# SCH_glacierone_2023-07-03.net
KiCad netlist of a schematic drawn in EasyEDA
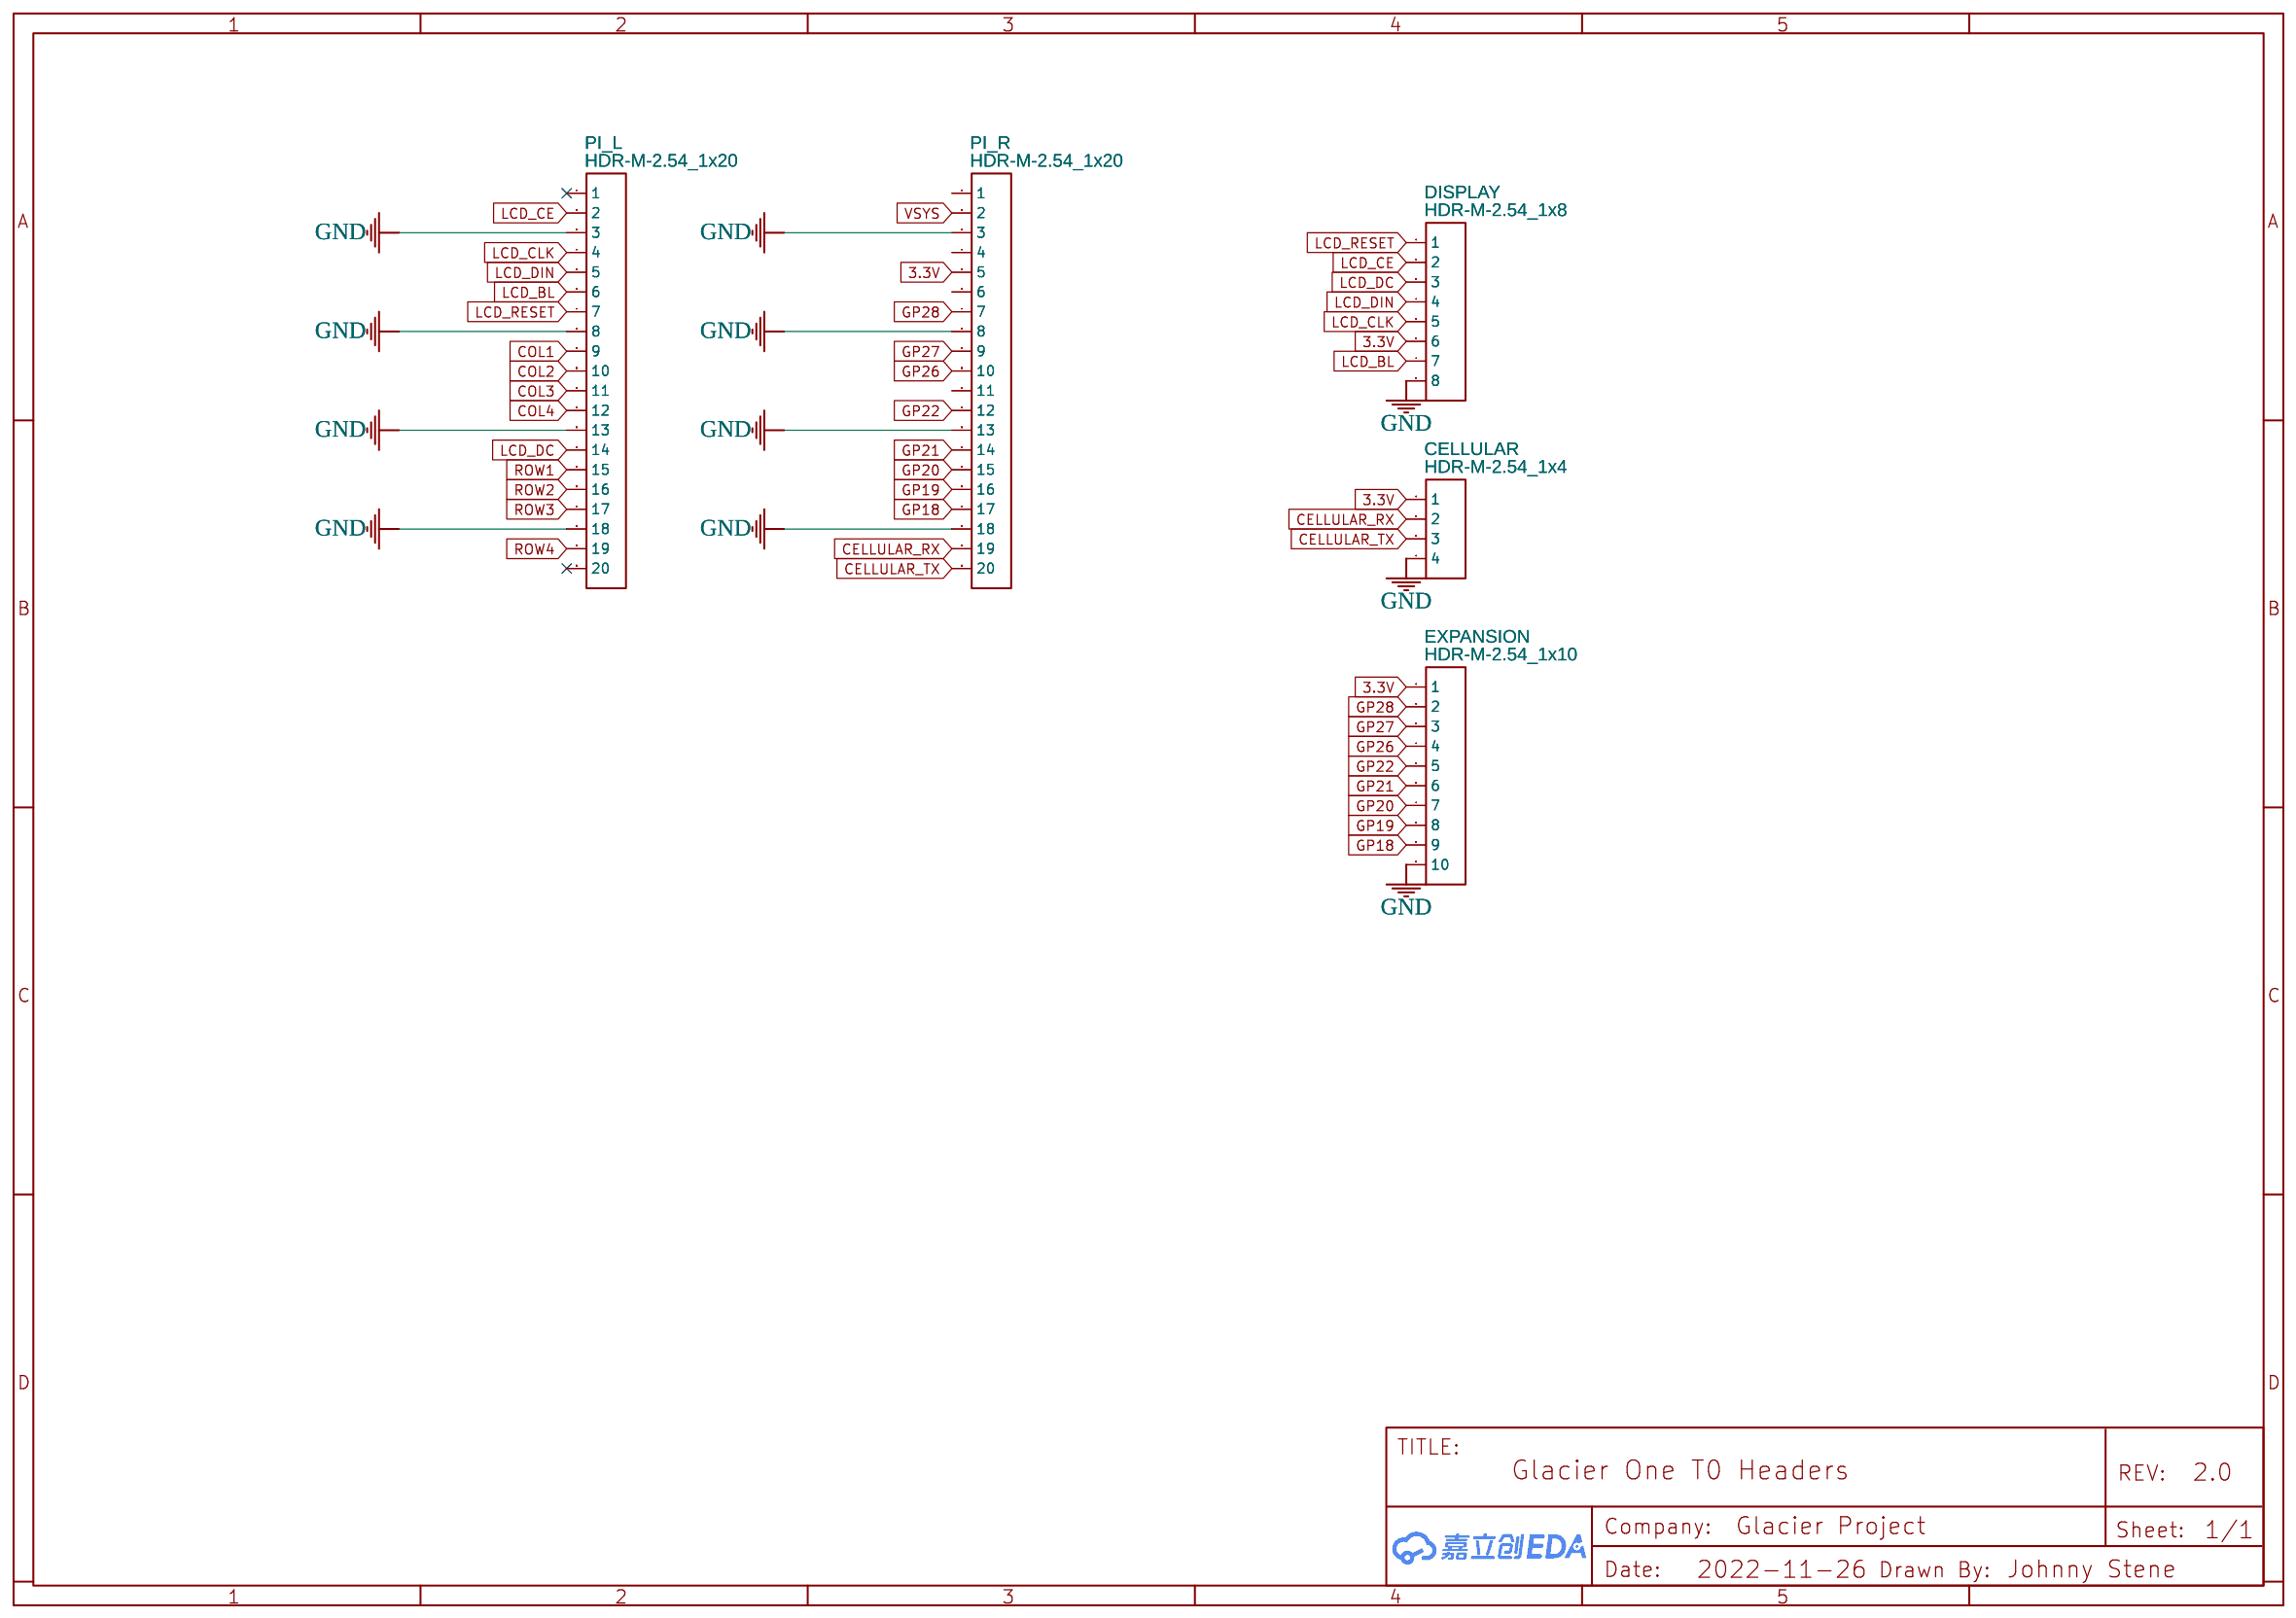
[diagram p0: Headers]
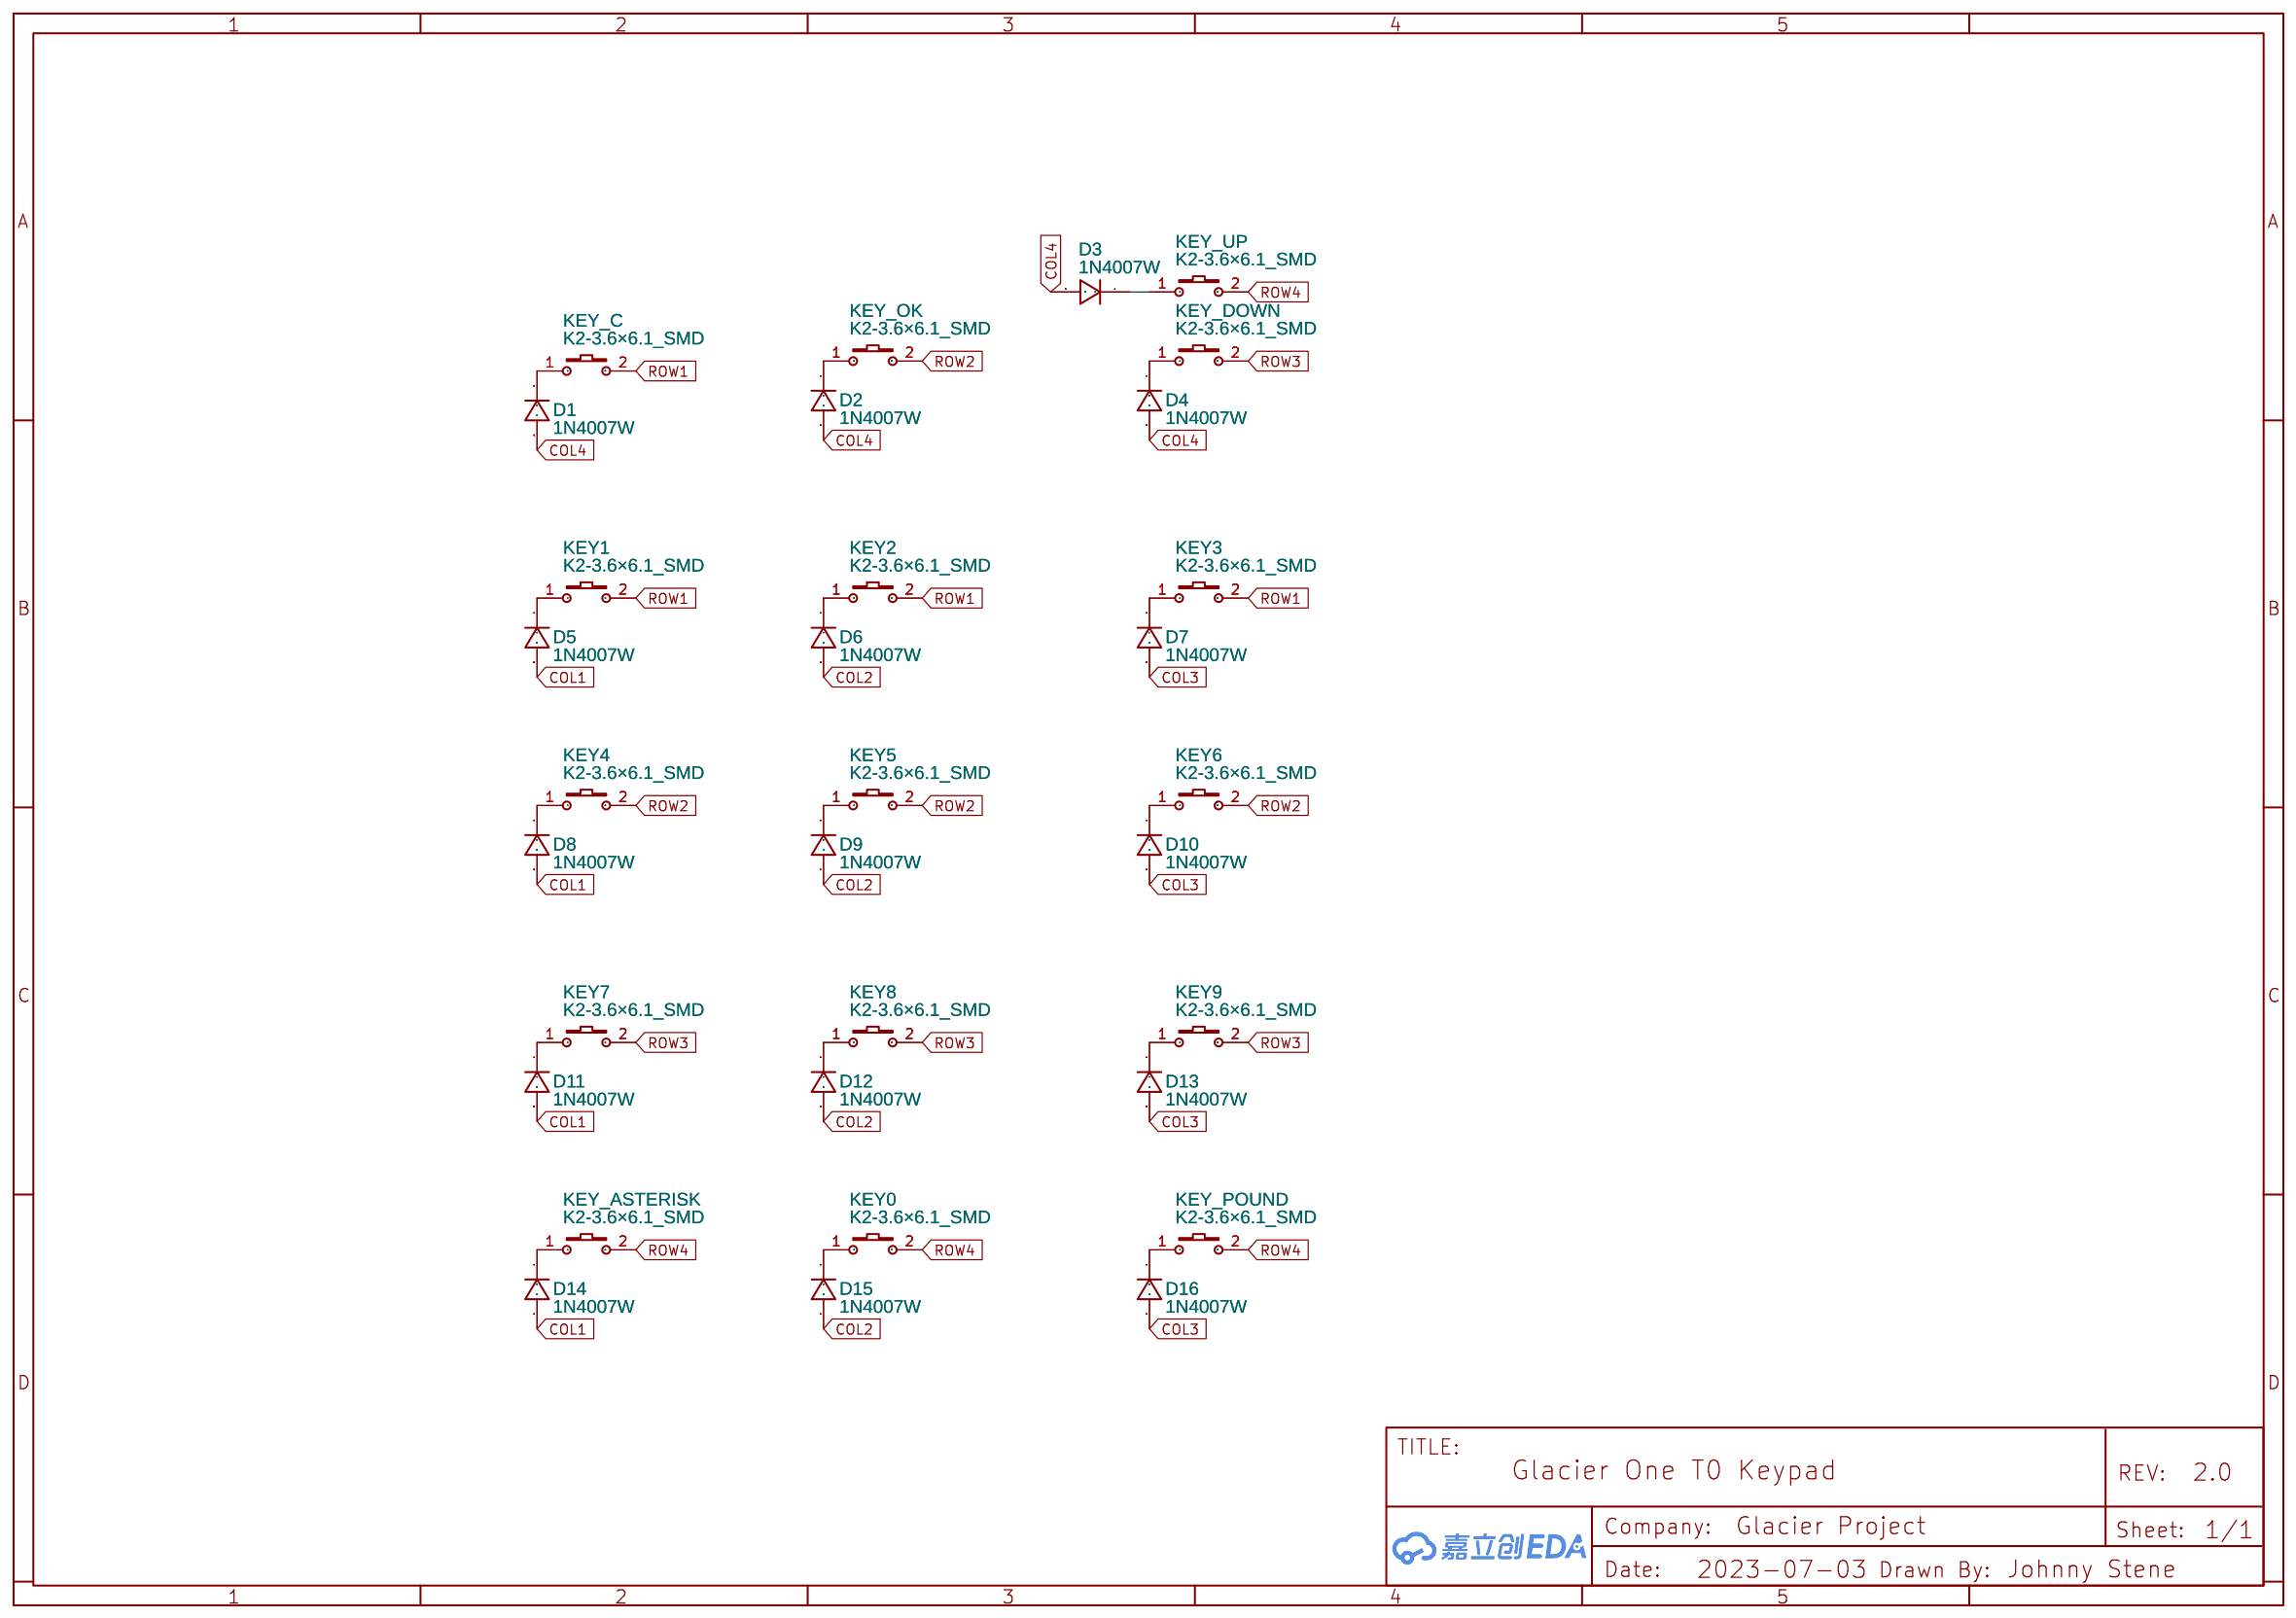
[diagram p1: Keypad]

(export (version "E")
  (design (tool "Eeschema 10.0.6"))
  (components
    (comp (ref "CELLULAR")
      (value "HDR-M-2.54_1x4")
      (fields (field (name "BOM_Supplier Part") "C124378"))
      (libsource (lib "") (part "HDR-M-2.54_1x4"))
    )
    (comp (ref "DISPLAY")
      (value "HDR-M-2.54_1x8")
      (fields (field (name "BOM_Supplier Part") "C190820"))
      (libsource (lib "") (part "HDR-M-2.54_1x8"))
    )
    (comp (ref "EXPANSION")
      (value "HDR-M-2.54_1x10")
      (fields (field (name "BOM_Supplier Part") "C57369"))
      (libsource (lib "") (part "HDR-M-2.54_1x10"))
    )
    (comp (ref "PI_L")
      (value "HDR-M-2.54_1x20")
      (fields (field (name "BOM_Supplier Part") "C50981"))
      (libsource (lib "") (part "HDR-M-2.54_1x20_1"))
    )
    (comp (ref "PI_R")
      (value "HDR-M-2.54_1x20")
      (fields (field (name "BOM_Supplier Part") "C50981"))
      (libsource (lib "") (part "HDR-M-2.54_1x20"))
    )
    (comp (ref "D1")
      (value "1N4007W")
      (fields (field (name "BOM_Supplier Part") "C328592"))
      (libsource (lib "") (part "1N4007W"))
    )
    (comp (ref "D2")
      (value "1N4007W")
      (fields (field (name "BOM_Supplier Part") "C328592"))
      (libsource (lib "") (part "1N4007W"))
    )
    (comp (ref "D3")
      (value "1N4007W")
      (fields (field (name "BOM_Supplier Part") "C328592"))
      (libsource (lib "") (part "1N4007W_1"))
    )
    (comp (ref "D4")
      (value "1N4007W")
      (fields (field (name "BOM_Supplier Part") "C328592"))
      (libsource (lib "") (part "1N4007W"))
    )
    (comp (ref "D5")
      (value "1N4007W")
      (fields (field (name "BOM_Supplier Part") "C328592"))
      (libsource (lib "") (part "1N4007W"))
    )
    (comp (ref "D6")
      (value "1N4007W")
      (fields (field (name "BOM_Supplier Part") "C328592"))
      (libsource (lib "") (part "1N4007W"))
    )
    (comp (ref "D7")
      (value "1N4007W")
      (fields (field (name "BOM_Supplier Part") "C328592"))
      (libsource (lib "") (part "1N4007W"))
    )
    (comp (ref "D8")
      (value "1N4007W")
      (fields (field (name "BOM_Supplier Part") "C328592"))
      (libsource (lib "") (part "1N4007W"))
    )
    (comp (ref "D9")
      (value "1N4007W")
      (fields (field (name "BOM_Supplier Part") "C328592"))
      (libsource (lib "") (part "1N4007W"))
    )
    (comp (ref "D10")
      (value "1N4007W")
      (fields (field (name "BOM_Supplier Part") "C328592"))
      (libsource (lib "") (part "1N4007W"))
    )
    (comp (ref "D11")
      (value "1N4007W")
      (fields (field (name "BOM_Supplier Part") "C328592"))
      (libsource (lib "") (part "1N4007W"))
    )
    (comp (ref "D12")
      (value "1N4007W")
      (fields (field (name "BOM_Supplier Part") "C328592"))
      (libsource (lib "") (part "1N4007W"))
    )
    (comp (ref "D13")
      (value "1N4007W")
      (fields (field (name "BOM_Supplier Part") "C328592"))
      (libsource (lib "") (part "1N4007W"))
    )
    (comp (ref "D14")
      (value "1N4007W")
      (fields (field (name "BOM_Supplier Part") "C328592"))
      (libsource (lib "") (part "1N4007W"))
    )
    (comp (ref "D15")
      (value "1N4007W")
      (fields (field (name "BOM_Supplier Part") "C328592"))
      (libsource (lib "") (part "1N4007W"))
    )
    (comp (ref "D16")
      (value "1N4007W")
      (fields (field (name "BOM_Supplier Part") "C328592"))
      (libsource (lib "") (part "1N4007W"))
    )
    (comp (ref "KEY0")
      (value "K2-3.6×6.1_SMD")
      (fields
        (field (name "BOM_Manufacturer Part") "K2-1107ST-A4SW-06")
        (field (name "BOM_Supplier Part") "C118141")
      )
      (libsource (lib "") (part "K2-3.6×6.1_SMD_2"))
    )
    (comp (ref "KEY1")
      (value "K2-3.6×6.1_SMD")
      (fields
        (field (name "BOM_Manufacturer Part") "K2-1107ST-A4SW-06")
        (field (name "BOM_Supplier Part") "C118141")
      )
      (libsource (lib "") (part "K2-3.6×6.1_SMD_2"))
    )
    (comp (ref "KEY2")
      (value "K2-3.6×6.1_SMD")
      (fields
        (field (name "BOM_Manufacturer Part") "K2-1107ST-A4SW-06")
        (field (name "BOM_Supplier Part") "C118141")
      )
      (libsource (lib "") (part "K2-3.6×6.1_SMD_2"))
    )
    (comp (ref "KEY3")
      (value "K2-3.6×6.1_SMD")
      (fields
        (field (name "BOM_Manufacturer Part") "K2-1107ST-A4SW-06")
        (field (name "BOM_Supplier Part") "C118141")
      )
      (libsource (lib "") (part "K2-3.6×6.1_SMD_2"))
    )
    (comp (ref "KEY4")
      (value "K2-3.6×6.1_SMD")
      (fields
        (field (name "BOM_Manufacturer Part") "K2-1107ST-A4SW-06")
        (field (name "BOM_Supplier Part") "C118141")
      )
      (libsource (lib "") (part "K2-3.6×6.1_SMD_2"))
    )
    (comp (ref "KEY5")
      (value "K2-3.6×6.1_SMD")
      (fields
        (field (name "BOM_Manufacturer Part") "K2-1107ST-A4SW-06")
        (field (name "BOM_Supplier Part") "C118141")
      )
      (libsource (lib "") (part "K2-3.6×6.1_SMD_2"))
    )
    (comp (ref "KEY6")
      (value "K2-3.6×6.1_SMD")
      (fields
        (field (name "BOM_Manufacturer Part") "K2-1107ST-A4SW-06")
        (field (name "BOM_Supplier Part") "C118141")
      )
      (libsource (lib "") (part "K2-3.6×6.1_SMD_2"))
    )
    (comp (ref "KEY7")
      (value "K2-3.6×6.1_SMD")
      (fields
        (field (name "BOM_Manufacturer Part") "K2-1107ST-A4SW-06")
        (field (name "BOM_Supplier Part") "C118141")
      )
      (libsource (lib "") (part "K2-3.6×6.1_SMD_2"))
    )
    (comp (ref "KEY8")
      (value "K2-3.6×6.1_SMD")
      (fields
        (field (name "BOM_Manufacturer Part") "K2-1107ST-A4SW-06")
        (field (name "BOM_Supplier Part") "C118141")
      )
      (libsource (lib "") (part "K2-3.6×6.1_SMD_2"))
    )
    (comp (ref "KEY9")
      (value "K2-3.6×6.1_SMD")
      (fields
        (field (name "BOM_Manufacturer Part") "K2-1107ST-A4SW-06")
        (field (name "BOM_Supplier Part") "C118141")
      )
      (libsource (lib "") (part "K2-3.6×6.1_SMD_2"))
    )
    (comp (ref "KEY_ASTERISK")
      (value "K2-3.6×6.1_SMD")
      (fields
        (field (name "BOM_Manufacturer Part") "K2-1107ST-A4SW-06")
        (field (name "BOM_Supplier Part") "C118141")
      )
      (libsource (lib "") (part "K2-3.6×6.1_SMD_1"))
    )
    (comp (ref "KEY_C")
      (value "K2-3.6×6.1_SMD")
      (fields
        (field (name "BOM_Manufacturer Part") "K2-1107ST-A4SW-06")
        (field (name "BOM_Supplier Part") "C118141")
      )
      (libsource (lib "") (part "K2-3.6×6.1_SMD_6"))
    )
    (comp (ref "KEY_DOWN")
      (value "K2-3.6×6.1_SMD")
      (fields
        (field (name "BOM_Manufacturer Part") "K2-1107ST-A4SW-06")
        (field (name "BOM_Supplier Part") "C118141")
      )
      (libsource (lib "") (part "K2-3.6×6.1_SMD_4"))
    )
    (comp (ref "KEY_OK")
      (value "K2-3.6×6.1_SMD")
      (fields
        (field (name "BOM_Manufacturer Part") "K2-1107ST-A4SW-06")
        (field (name "BOM_Supplier Part") "C118141")
      )
      (libsource (lib "") (part "K2-3.6×6.1_SMD_5"))
    )
    (comp (ref "KEY_POUND")
      (value "K2-3.6×6.1_SMD")
      (fields
        (field (name "BOM_Manufacturer Part") "K2-1107ST-A4SW-06")
        (field (name "BOM_Supplier Part") "C118141")
      )
      (libsource (lib "") (part "K2-3.6×6.1_SMD_3"))
    )
    (comp (ref "KEY_UP")
      (value "K2-3.6×6.1_SMD")
      (fields
        (field (name "BOM_Manufacturer Part") "K2-1107ST-A4SW-06")
        (field (name "BOM_Supplier Part") "C118141")
      )
      (libsource (lib "") (part "K2-3.6×6.1_SMD"))
    )
  )
  (nets
    (net (code "1") (name "3.3V") (class "Default")
      (node (ref "CELLULAR") (pin "1") (pinfunction "1_1") (pintype "unspecified"))
      (node (ref "DISPLAY") (pin "6") (pinfunction "6_6") (pintype "unspecified"))
      (node (ref "EXPANSION") (pin "1") (pinfunction "1_1") (pintype "unspecified"))
      (node (ref "PI_R") (pin "5") (pinfunction "5_5") (pintype "unspecified"))
    )
    (net (code "2") (name "CELLULAR_RX") (class "Default")
      (node (ref "CELLULAR") (pin "2") (pinfunction "2_2") (pintype "unspecified"))
      (node (ref "PI_R") (pin "19") (pinfunction "19_19") (pintype "unspecified"))
    )
    (net (code "3") (name "CELLULAR_TX") (class "Default")
      (node (ref "CELLULAR") (pin "3") (pinfunction "3_3") (pintype "unspecified"))
      (node (ref "PI_R") (pin "20") (pinfunction "20_20") (pintype "unspecified"))
    )
    (net (code "4") (name "COL1") (class "Default")
      (node (ref "D11") (pin "2") (pinfunction "2_2") (pintype "unspecified"))
      (node (ref "D14") (pin "2") (pinfunction "2_2") (pintype "unspecified"))
      (node (ref "D5") (pin "2") (pinfunction "2_2") (pintype "unspecified"))
      (node (ref "D8") (pin "2") (pinfunction "2_2") (pintype "unspecified"))
      (node (ref "PI_L") (pin "9") (pinfunction "9_9") (pintype "unspecified"))
    )
    (net (code "5") (name "COL2") (class "Default")
      (node (ref "D12") (pin "2") (pinfunction "2_2") (pintype "unspecified"))
      (node (ref "D15") (pin "2") (pinfunction "2_2") (pintype "unspecified"))
      (node (ref "D6") (pin "2") (pinfunction "2_2") (pintype "unspecified"))
      (node (ref "D9") (pin "2") (pinfunction "2_2") (pintype "unspecified"))
      (node (ref "PI_L") (pin "10") (pinfunction "10_10") (pintype "unspecified"))
    )
    (net (code "6") (name "COL3") (class "Default")
      (node (ref "D10") (pin "2") (pinfunction "2_2") (pintype "unspecified"))
      (node (ref "D13") (pin "2") (pinfunction "2_2") (pintype "unspecified"))
      (node (ref "D16") (pin "2") (pinfunction "2_2") (pintype "unspecified"))
      (node (ref "D7") (pin "2") (pinfunction "2_2") (pintype "unspecified"))
      (node (ref "PI_L") (pin "11") (pinfunction "11_11") (pintype "unspecified"))
    )
    (net (code "7") (name "COL4") (class "Default")
      (node (ref "D1") (pin "2") (pinfunction "2_2") (pintype "unspecified"))
      (node (ref "D2") (pin "2") (pinfunction "2_2") (pintype "unspecified"))
      (node (ref "D3") (pin "2") (pinfunction "2_2") (pintype "unspecified"))
      (node (ref "D4") (pin "2") (pinfunction "2_2") (pintype "unspecified"))
      (node (ref "PI_L") (pin "12") (pinfunction "12_12") (pintype "unspecified"))
    )
    (net (code "8") (name "GND") (class "Default")
      (node (ref "CELLULAR") (pin "4") (pinfunction "4_4") (pintype "unspecified"))
      (node (ref "DISPLAY") (pin "8") (pinfunction "8_8") (pintype "unspecified"))
      (node (ref "EXPANSION") (pin "10") (pinfunction "10_10") (pintype "unspecified"))
      (node (ref "PI_L") (pin "13") (pinfunction "13_13") (pintype "unspecified"))
      (node (ref "PI_L") (pin "18") (pinfunction "18_18") (pintype "unspecified"))
      (node (ref "PI_L") (pin "3") (pinfunction "3_3") (pintype "unspecified"))
      (node (ref "PI_L") (pin "8") (pinfunction "8_8") (pintype "unspecified"))
      (node (ref "PI_R") (pin "13") (pinfunction "13_13") (pintype "unspecified"))
      (node (ref "PI_R") (pin "18") (pinfunction "18_18") (pintype "unspecified"))
      (node (ref "PI_R") (pin "3") (pinfunction "3_3") (pintype "unspecified"))
      (node (ref "PI_R") (pin "8") (pinfunction "8_8") (pintype "unspecified"))
    )
    (net (code "9") (name "GP18") (class "Default")
      (node (ref "EXPANSION") (pin "9") (pinfunction "9_9") (pintype "unspecified"))
      (node (ref "PI_R") (pin "17") (pinfunction "17_17") (pintype "unspecified"))
    )
    (net (code "10") (name "GP19") (class "Default")
      (node (ref "EXPANSION") (pin "8") (pinfunction "8_8") (pintype "unspecified"))
      (node (ref "PI_R") (pin "16") (pinfunction "16_16") (pintype "unspecified"))
    )
    (net (code "11") (name "GP20") (class "Default")
      (node (ref "EXPANSION") (pin "7") (pinfunction "7_7") (pintype "unspecified"))
      (node (ref "PI_R") (pin "15") (pinfunction "15_15") (pintype "unspecified"))
    )
    (net (code "12") (name "GP21") (class "Default")
      (node (ref "EXPANSION") (pin "6") (pinfunction "6_6") (pintype "unspecified"))
      (node (ref "PI_R") (pin "14") (pinfunction "14_14") (pintype "unspecified"))
    )
    (net (code "13") (name "GP22") (class "Default")
      (node (ref "EXPANSION") (pin "5") (pinfunction "5_5") (pintype "unspecified"))
      (node (ref "PI_R") (pin "12") (pinfunction "12_12") (pintype "unspecified"))
    )
    (net (code "14") (name "GP26") (class "Default")
      (node (ref "EXPANSION") (pin "4") (pinfunction "4_4") (pintype "unspecified"))
      (node (ref "PI_R") (pin "10") (pinfunction "10_10") (pintype "unspecified"))
    )
    (net (code "15") (name "GP27") (class "Default")
      (node (ref "EXPANSION") (pin "3") (pinfunction "3_3") (pintype "unspecified"))
      (node (ref "PI_R") (pin "9") (pinfunction "9_9") (pintype "unspecified"))
    )
    (net (code "16") (name "GP28") (class "Default")
      (node (ref "EXPANSION") (pin "2") (pinfunction "2_2") (pintype "unspecified"))
      (node (ref "PI_R") (pin "7") (pinfunction "7_7") (pintype "unspecified"))
    )
    (net (code "17") (name "LCD_BL") (class "Default")
      (node (ref "DISPLAY") (pin "7") (pinfunction "7_7") (pintype "unspecified"))
      (node (ref "PI_L") (pin "6") (pinfunction "6_6") (pintype "unspecified"))
    )
    (net (code "18") (name "LCD_CE") (class "Default")
      (node (ref "DISPLAY") (pin "2") (pinfunction "2_2") (pintype "unspecified"))
      (node (ref "PI_L") (pin "2") (pinfunction "2_2") (pintype "unspecified"))
    )
    (net (code "19") (name "LCD_CLK") (class "Default")
      (node (ref "DISPLAY") (pin "5") (pinfunction "5_5") (pintype "unspecified"))
      (node (ref "PI_L") (pin "4") (pinfunction "4_4") (pintype "unspecified"))
    )
    (net (code "20") (name "LCD_DC") (class "Default")
      (node (ref "DISPLAY") (pin "3") (pinfunction "3_3") (pintype "unspecified"))
      (node (ref "PI_L") (pin "14") (pinfunction "14_14") (pintype "unspecified"))
    )
    (net (code "21") (name "LCD_DIN") (class "Default")
      (node (ref "DISPLAY") (pin "4") (pinfunction "4_4") (pintype "unspecified"))
      (node (ref "PI_L") (pin "5") (pinfunction "5_5") (pintype "unspecified"))
    )
    (net (code "22") (name "LCD_RESET") (class "Default")
      (node (ref "DISPLAY") (pin "1") (pinfunction "1_1") (pintype "unspecified"))
      (node (ref "PI_L") (pin "7") (pinfunction "7_7") (pintype "unspecified"))
    )
    (net (code "23") (name "Net-(D1-Pad1)") (class "Default")
      (node (ref "D1") (pin "1") (pinfunction "1_1") (pintype "unspecified"))
      (node (ref "KEY_C") (pin "1") (pinfunction "1_1") (pintype "unspecified"))
    )
    (net (code "24") (name "Net-(D2-Pad1)") (class "Default")
      (node (ref "D2") (pin "1") (pinfunction "1_1") (pintype "unspecified"))
      (node (ref "KEY_OK") (pin "1") (pinfunction "1_1") (pintype "unspecified"))
    )
    (net (code "25") (name "Net-(D3-Pad1)") (class "Default")
      (node (ref "D3") (pin "1") (pinfunction "1_1") (pintype "unspecified"))
      (node (ref "KEY_UP") (pin "1") (pinfunction "1_1") (pintype "unspecified"))
    )
    (net (code "26") (name "Net-(D4-Pad1)") (class "Default")
      (node (ref "D4") (pin "1") (pinfunction "1_1") (pintype "unspecified"))
      (node (ref "KEY_DOWN") (pin "1") (pinfunction "1_1") (pintype "unspecified"))
    )
    (net (code "27") (name "Net-(D5-Pad1)") (class "Default")
      (node (ref "D5") (pin "1") (pinfunction "1_1") (pintype "unspecified"))
      (node (ref "KEY1") (pin "1") (pinfunction "1_1") (pintype "unspecified"))
    )
    (net (code "28") (name "Net-(D6-Pad1)") (class "Default")
      (node (ref "D6") (pin "1") (pinfunction "1_1") (pintype "unspecified"))
      (node (ref "KEY2") (pin "1") (pinfunction "1_1") (pintype "unspecified"))
    )
    (net (code "29") (name "Net-(D7-Pad1)") (class "Default")
      (node (ref "D7") (pin "1") (pinfunction "1_1") (pintype "unspecified"))
      (node (ref "KEY3") (pin "1") (pinfunction "1_1") (pintype "unspecified"))
    )
    (net (code "30") (name "Net-(D8-Pad1)") (class "Default")
      (node (ref "D8") (pin "1") (pinfunction "1_1") (pintype "unspecified"))
      (node (ref "KEY4") (pin "1") (pinfunction "1_1") (pintype "unspecified"))
    )
    (net (code "31") (name "Net-(D9-Pad1)") (class "Default")
      (node (ref "D9") (pin "1") (pinfunction "1_1") (pintype "unspecified"))
      (node (ref "KEY5") (pin "1") (pinfunction "1_1") (pintype "unspecified"))
    )
    (net (code "32") (name "Net-(D10-Pad1)") (class "Default")
      (node (ref "D10") (pin "1") (pinfunction "1_1") (pintype "unspecified"))
      (node (ref "KEY6") (pin "1") (pinfunction "1_1") (pintype "unspecified"))
    )
    (net (code "33") (name "Net-(D11-Pad1)") (class "Default")
      (node (ref "D11") (pin "1") (pinfunction "1_1") (pintype "unspecified"))
      (node (ref "KEY7") (pin "1") (pinfunction "1_1") (pintype "unspecified"))
    )
    (net (code "34") (name "Net-(D12-Pad1)") (class "Default")
      (node (ref "D12") (pin "1") (pinfunction "1_1") (pintype "unspecified"))
      (node (ref "KEY8") (pin "1") (pinfunction "1_1") (pintype "unspecified"))
    )
    (net (code "35") (name "Net-(D13-Pad1)") (class "Default")
      (node (ref "D13") (pin "1") (pinfunction "1_1") (pintype "unspecified"))
      (node (ref "KEY9") (pin "1") (pinfunction "1_1") (pintype "unspecified"))
    )
    (net (code "36") (name "Net-(D14-Pad1)") (class "Default")
      (node (ref "D14") (pin "1") (pinfunction "1_1") (pintype "unspecified"))
      (node (ref "KEY_ASTERISK") (pin "1") (pinfunction "1_1") (pintype "unspecified"))
    )
    (net (code "37") (name "Net-(D15-Pad1)") (class "Default")
      (node (ref "D15") (pin "1") (pinfunction "1_1") (pintype "unspecified"))
      (node (ref "KEY0") (pin "1") (pinfunction "1_1") (pintype "unspecified"))
    )
    (net (code "38") (name "Net-(D16-Pad1)") (class "Default")
      (node (ref "D16") (pin "1") (pinfunction "1_1") (pintype "unspecified"))
      (node (ref "KEY_POUND") (pin "1") (pinfunction "1_1") (pintype "unspecified"))
    )
    (net (code "39") (name "ROW1") (class "Default")
      (node (ref "KEY1") (pin "2") (pinfunction "2_2") (pintype "unspecified"))
      (node (ref "KEY2") (pin "2") (pinfunction "2_2") (pintype "unspecified"))
      (node (ref "KEY3") (pin "2") (pinfunction "2_2") (pintype "unspecified"))
      (node (ref "KEY_C") (pin "2") (pinfunction "2_2") (pintype "unspecified"))
      (node (ref "PI_L") (pin "15") (pinfunction "15_15") (pintype "unspecified"))
    )
    (net (code "40") (name "ROW2") (class "Default")
      (node (ref "KEY4") (pin "2") (pinfunction "2_2") (pintype "unspecified"))
      (node (ref "KEY5") (pin "2") (pinfunction "2_2") (pintype "unspecified"))
      (node (ref "KEY6") (pin "2") (pinfunction "2_2") (pintype "unspecified"))
      (node (ref "KEY_OK") (pin "2") (pinfunction "2_2") (pintype "unspecified"))
      (node (ref "PI_L") (pin "16") (pinfunction "16_16") (pintype "unspecified"))
    )
    (net (code "41") (name "ROW3") (class "Default")
      (node (ref "KEY7") (pin "2") (pinfunction "2_2") (pintype "unspecified"))
      (node (ref "KEY8") (pin "2") (pinfunction "2_2") (pintype "unspecified"))
      (node (ref "KEY9") (pin "2") (pinfunction "2_2") (pintype "unspecified"))
      (node (ref "KEY_DOWN") (pin "2") (pinfunction "2_2") (pintype "unspecified"))
      (node (ref "PI_L") (pin "17") (pinfunction "17_17") (pintype "unspecified"))
    )
    (net (code "42") (name "ROW4") (class "Default")
      (node (ref "KEY0") (pin "2") (pinfunction "2_2") (pintype "unspecified"))
      (node (ref "KEY_ASTERISK") (pin "2") (pinfunction "2_2") (pintype "unspecified"))
      (node (ref "KEY_POUND") (pin "2") (pinfunction "2_2") (pintype "unspecified"))
      (node (ref "KEY_UP") (pin "2") (pinfunction "2_2") (pintype "unspecified"))
      (node (ref "PI_L") (pin "19") (pinfunction "19_19") (pintype "unspecified"))
    )
    (net (code "43") (name "VSYS") (class "Default")
      (node (ref "PI_R") (pin "2") (pinfunction "2_2") (pintype "unspecified"))
    )
    (net (code "44") (name "unconnected-(PI_L-Pad1)") (class "Default")
      (node (ref "PI_L") (pin "1") (pinfunction "1_1") (pintype "unspecified+no_connect"))
    )
    (net (code "45") (name "unconnected-(PI_L-Pad20)") (class "Default")
      (node (ref "PI_L") (pin "20") (pinfunction "20_20") (pintype "unspecified+no_connect"))
    )
    (net (code "46") (name "unconnected-(PI_R-Pad1)") (class "Default")
      (node (ref "PI_R") (pin "1") (pinfunction "1_1") (pintype "unspecified"))
    )
    (net (code "47") (name "unconnected-(PI_R-Pad4)") (class "Default")
      (node (ref "PI_R") (pin "4") (pinfunction "4_4") (pintype "unspecified"))
    )
    (net (code "48") (name "unconnected-(PI_R-Pad6)") (class "Default")
      (node (ref "PI_R") (pin "6") (pinfunction "6_6") (pintype "unspecified"))
    )
    (net (code "49") (name "unconnected-(PI_R-Pad11)") (class "Default")
      (node (ref "PI_R") (pin "11") (pinfunction "11_11") (pintype "unspecified"))
    )
  )
)
